# Supplies02.net
KiCad netlist of a schematic drawn in Altium Designer
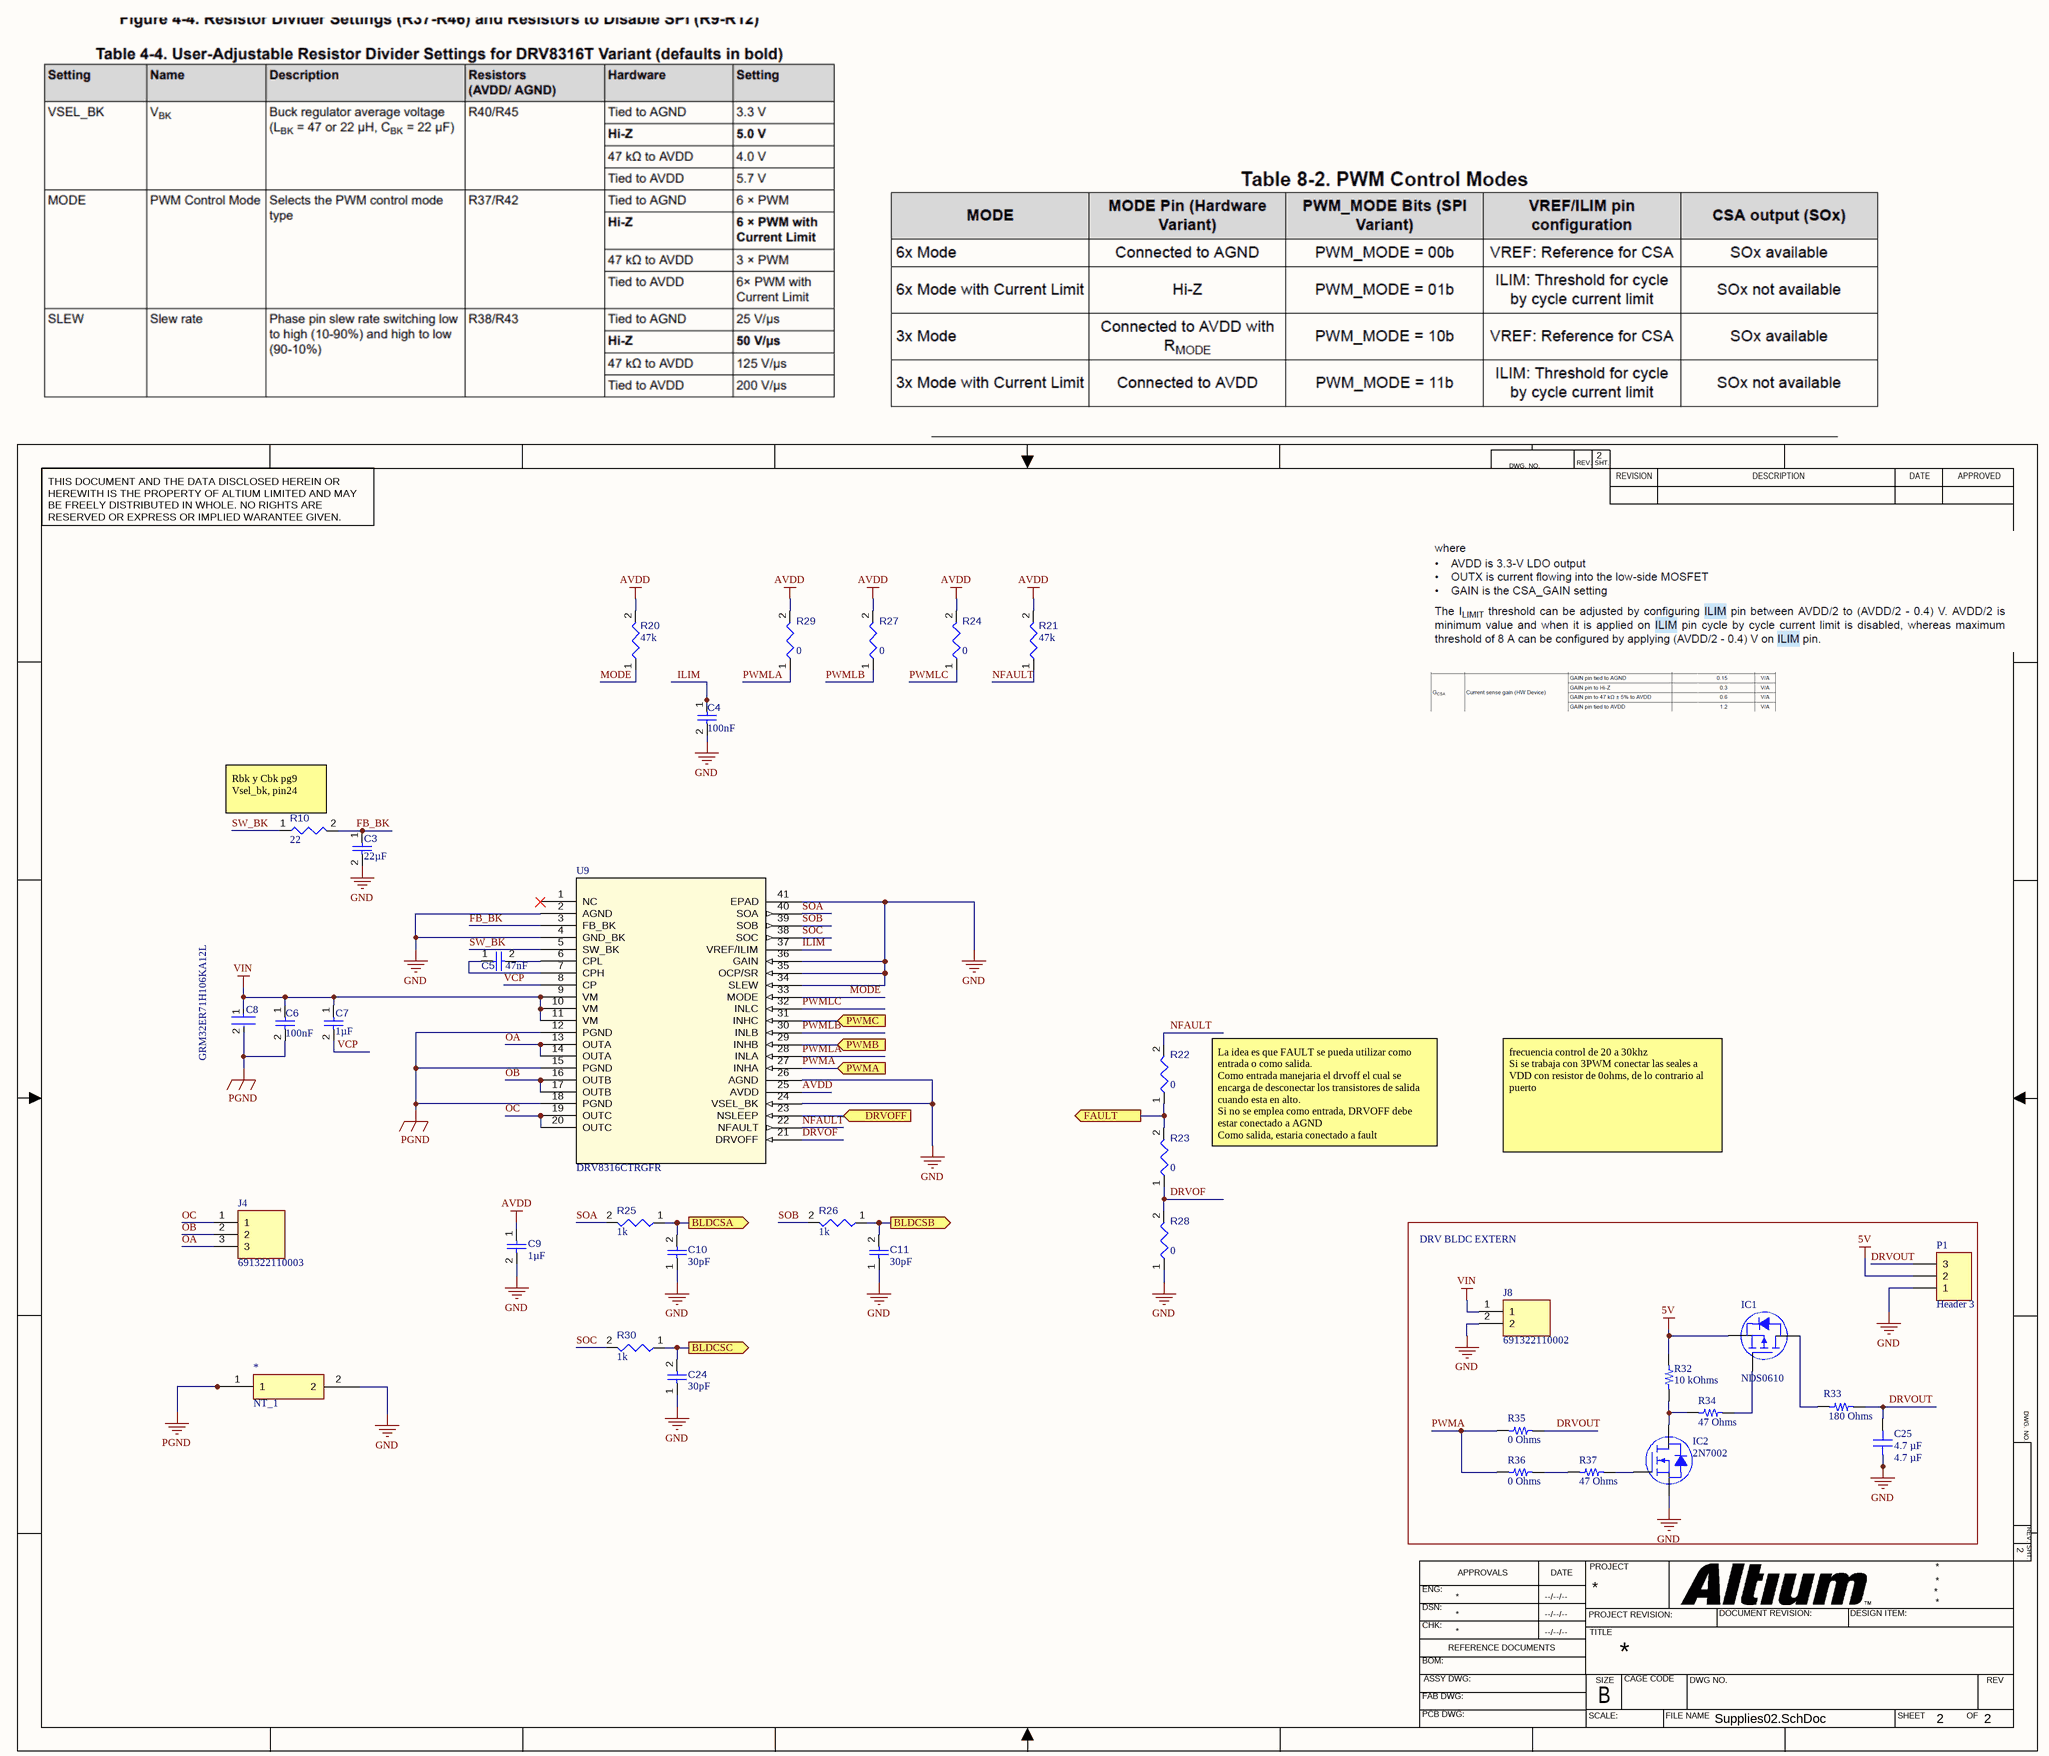
[diagram p0: Supplies02.SchDoc]

(export (version "E")
  (design (tool "Eeschema 10.0.6"))
  (components
    (comp (ref "*") (value "NT_1") (footprint "Net_Tie") (libsource (lib "net_tie") (part "NT_1")))
    (comp (ref "C3")
      (value "22µF")
      (footprint "CAPC0805(2012)145_L")
      (description "Chip Capacitor, 22µF +/-40%, 16V, 0805, Thickness 1.45 mm")
      (fields (field (name "TOLERANCE") "5%") (field (name "Comment") "Capacitor 22µF +/-40% 16V 0805"))
      (libsource (lib "UdeA") (part "CAP-NP-2"))
    )
    (comp (ref "C4")
      (value "100nF")
      (footprint "CAPC1608X90X40NL10T20")
      (description "Chip Capacitor, 100 nF, +/- 10%, 50 V, 0603 (1608 Metric)")
      (fields (field (name "TOLERANCE") "10%") (field (name "Comment") "Capacitor 100 nF +/-10% 50 V 0603"))
      (libsource (lib "UdeA") (part "CAP-NP-2"))
    )
    (comp (ref "C5")
      (value "47nF")
      (footprint "CAPC1608X90X40NL10T20")
      (description "Chip Capacitor, 100 nF, +/- 10%, 50 V, 0603 (1608 Metric)")
      (fields (field (name "TOLERANCE") "10%") (field (name "Comment") "Capacitor 100 nF +/-10% 50 V 0603"))
      (libsource (lib "UdeA") (part "CAP-NP-2"))
    )
    (comp (ref "C6")
      (value "100nF")
      (footprint "CAPC1608X90X40NL10T20")
      (description "Chip Capacitor, 100 nF, +/- 10%, 50 V, 0603 (1608 Metric)")
      (fields (field (name "TOLERANCE") "10%") (field (name "Comment") "Capacitor 100 nF +/-10% 50 V 0603"))
      (libsource (lib "UdeA") (part "CAP-NP-2"))
    )
    (comp (ref "C7")
      (value "1µF")
      (footprint "CAPC0805(2012)145_L")
      (description "Chip Capacitor, 22µF +/-40%, 16V, 0805, Thickness 1.45 mm")
      (fields (field (name "TOLERANCE") "5%") (field (name "Comment") "Capacitor 22µF +/-40% 16V 0805"))
      (libsource (lib "UdeA") (part "CAP-NP-2"))
    )
    (comp (ref "C8")
      (value "GRM32ER71H106KA12L")
      (footprint "FP-GRM32-MFG")
      (description "CAP CER 10UF 50V X7R 1210")
      (fields (field (name "TOLERANCE") "10%") (field (name "MANUFACTURER") "Murata"))
      (libsource (lib "Altium Content Vault") (part "11868f565c42a9108669ba33697ecf6"))
    )
    (comp (ref "C9")
      (value "1µF")
      (footprint "CAPC0805(2012)145_L")
      (description "Chip Capacitor, 22µF +/-40%, 16V, 0805, Thickness 1.45 mm")
      (fields (field (name "TOLERANCE") "5%") (field (name "Comment") "Capacitor 22µF +/-40% 16V 0805"))
      (libsource (lib "UdeA") (part "CAP-NP-2"))
    )
    (comp (ref "C10")
      (value "30pF")
      (footprint "CAPC1608X90X40NL10T20")
      (description "Chip Capacitor, 100 nF, +/- 10%, 50 V, 0603 (1608 Metric)")
      (fields (field (name "TOLERANCE") "10%") (field (name "Comment") "Capacitor 100 nF +/-10% 50 V 0603"))
      (libsource (lib "UdeA") (part "CAP-NP-2"))
    )
    (comp (ref "C11")
      (value "30pF")
      (footprint "CAPC1608X90X40NL10T20")
      (description "Chip Capacitor, 100 nF, +/- 10%, 50 V, 0603 (1608 Metric)")
      (fields (field (name "TOLERANCE") "10%") (field (name "Comment") "Capacitor 100 nF +/-10% 50 V 0603"))
      (libsource (lib "UdeA") (part "CAP-NP-2"))
    )
    (comp (ref "C24")
      (value "30pF")
      (footprint "CAPC1608X90X40NL10T20")
      (description "Chip Capacitor, 100 nF, +/- 10%, 50 V, 0603 (1608 Metric)")
      (fields (field (name "TOLERANCE") "10%") (field (name "Comment") "Capacitor 100 nF +/-10% 50 V 0603"))
      (libsource (lib "UdeA") (part "CAP-NP-2"))
    )
    (comp (ref "C25")
      (value "4.7 µF")
      (footprint "CAP 0805_2012")
      (description "CAP CER 4.7UF 6.3V X7R 0805")
      (fields
        (field (name "PART NUMBER") "C0805X475J9RACAUTO")
        (field (name "CAPACITANCE") "4.7 µF")
        (field (name "MANUFACTURER") "KEMET")
      )
      (libsource (lib "Celestial Altium Library - altium_library") (part "Capacitor"))
    )
    (comp (ref "IC1")
      (value "NDS0610")
      (footprint "ON SEMI SOT-23-3")
      (description "MOSFET P-CH 60V 120MA SOT-23")
      (fields (field (name "MANUFACTURER") "ON Semiconductor"))
      (libsource (lib "Celestial Altium Library - altium_library") (part "ON SEMI MOSFET P-CH SOT-23-3"))
    )
    (comp (ref "IC2")
      (value "2N7002")
      (footprint "ON SEMI SOT-23-3")
      (description "MOSFET N-CH 60V 115MA SOT-23")
      (fields (field (name "MANUFACTURER") "ON Semiconductor"))
      (libsource (lib "Celestial Altium Library - altium_library") (part "ON SEMI MOSFET N-CH SOT-23-3"))
    )
    (comp (ref "J4")
      (value "691322110003")
      (footprint "SHDRRA3W80P0X350_1X3_1190X920X700P")
      (fields (field (name "MOUSER PART NUMBER") "710-691322110003"))
      (libsource (lib "691322110003") (part "691322110003"))
    )
    (comp (ref "J8")
      (value "691322110002")
      (footprint "SHDRRA2W80P0X350_1X2_840X920X720P")
      (description "WR-TBL Terminal block - serie 3221")
      (fields (field (name "MOUSER PART NUMBER") "710-691322110002"))
      (libsource (lib "691322110002") (part "691322110002"))
    )
    (comp (ref "P1")
      (value "Header 3")
      (footprint "HDR1X3")
      (description "Header, 3-Pin")
      (fields (field (name "PUBLISHER") "Altium Limited"))
      (libsource (lib "Miscellaneous Connectors") (part "Header 3"))
    )
    (comp (ref "R10")
      (value "22")
      (footprint "RESC1608X55X25ML10T15")
      (description "Chip Resistor, 10 KOhm, +/- 1%, 01 W, -55 to 155 degC, 0603 (1608 Metric)")
      (fields (field (name "POWER") "100mW") (field (name "TOLERANCE") "1%"))
      (libsource (lib "UdeA") (part "RES-2"))
    )
    (comp (ref "R20")
      (value "47k")
      (footprint "RESC1608X55X25ML10T15")
      (description "Chip Resistor, 10 KOhm, +/- 1%, 01 W, -55 to 155 degC, 0603 (1608 Metric)")
      (fields (field (name "POWER") "100mW") (field (name "TOLERANCE") "1%"))
      (libsource (lib "UdeA") (part "RES-2"))
    )
    (comp (ref "R21")
      (value "47k")
      (footprint "RESC1608X55X25ML10T15")
      (description "Chip Resistor, 10 KOhm, +/- 1%, 01 W, -55 to 155 degC, 0603 (1608 Metric)")
      (fields (field (name "POWER") "100mW") (field (name "TOLERANCE") "1%"))
      (libsource (lib "UdeA") (part "RES-2"))
    )
    (comp (ref "R22")
      (value "0")
      (footprint "RESC1608X55X25ML10T15")
      (description "Chip Resistor, 10 KOhm, +/- 1%, 01 W, -55 to 155 degC, 0603 (1608 Metric)")
      (fields (field (name "POWER") "100mW") (field (name "TOLERANCE") "1%"))
      (libsource (lib "UdeA") (part "RES-2"))
    )
    (comp (ref "R23")
      (value "0")
      (footprint "RESC1608X55X25ML10T15")
      (description "Chip Resistor, 10 KOhm, +/- 1%, 01 W, -55 to 155 degC, 0603 (1608 Metric)")
      (fields (field (name "POWER") "100mW") (field (name "TOLERANCE") "1%"))
      (libsource (lib "UdeA") (part "RES-2"))
    )
    (comp (ref "R24")
      (value "0")
      (footprint "RESC1608X55X25ML10T15")
      (description "Chip Resistor, 10 KOhm, +/- 1%, 01 W, -55 to 155 degC, 0603 (1608 Metric)")
      (fields (field (name "POWER") "100mW") (field (name "TOLERANCE") "1%"))
      (libsource (lib "UdeA") (part "RES-2"))
    )
    (comp (ref "R25")
      (value "1k")
      (footprint "RESC1608X55X25ML10T15")
      (description "Chip Resistor, 10 KOhm, +/- 1%, 01 W, -55 to 155 degC, 0603 (1608 Metric)")
      (fields (field (name "POWER") "100mW") (field (name "TOLERANCE") "1%"))
      (libsource (lib "UdeA") (part "RES-2"))
    )
    (comp (ref "R26")
      (value "1k")
      (footprint "RESC1608X55X25ML10T15")
      (description "Chip Resistor, 10 KOhm, +/- 1%, 01 W, -55 to 155 degC, 0603 (1608 Metric)")
      (fields (field (name "POWER") "100mW") (field (name "TOLERANCE") "1%"))
      (libsource (lib "UdeA") (part "RES-2"))
    )
    (comp (ref "R27")
      (value "0")
      (footprint "RESC1608X55X25ML10T15")
      (description "Chip Resistor, 10 KOhm, +/- 1%, 01 W, -55 to 155 degC, 0603 (1608 Metric)")
      (fields (field (name "POWER") "100mW") (field (name "TOLERANCE") "1%"))
      (libsource (lib "UdeA") (part "RES-2"))
    )
    (comp (ref "R28")
      (value "0")
      (footprint "RESC1608X55X25ML10T15")
      (description "Chip Resistor, 10 KOhm, +/- 1%, 01 W, -55 to 155 degC, 0603 (1608 Metric)")
      (fields (field (name "POWER") "100mW") (field (name "TOLERANCE") "1%"))
      (libsource (lib "UdeA") (part "RES-2"))
    )
    (comp (ref "R29")
      (value "0")
      (footprint "RESC1608X55X25ML10T15")
      (description "Chip Resistor, 10 KOhm, +/- 1%, 01 W, -55 to 155 degC, 0603 (1608 Metric)")
      (fields (field (name "POWER") "100mW") (field (name "TOLERANCE") "1%"))
      (libsource (lib "altium-import") (part "root_1_RES-2_"))
    )
    (comp (ref "R30")
      (value "1k")
      (footprint "RESC1608X55X25ML10T15")
      (description "Chip Resistor, 10 KOhm, +/- 1%, 01 W, -55 to 155 degC, 0603 (1608 Metric)")
      (fields (field (name "POWER") "100mW") (field (name "TOLERANCE") "1%"))
      (libsource (lib "UdeA") (part "RES-2"))
    )
    (comp (ref "R32")
      (value "10 kOhms")
      (footprint "YAGEO RES 0603_1608")
      (description "RES SMD 10K OHM 0.5% 1/10W 0603")
      (fields (field (name "PART NUMBER") "RT0603DRD0710KL") (field (name "MANUFACTURER") "Yageo"))
      (libsource (lib "Celestial Altium Library - altium_library") (part "Resistor"))
    )
    (comp (ref "R33")
      (value "180 Ohms")
      (footprint "YAGEO RES 0603_1608")
      (description "RES SMD 180 OHM 0.1% 1/10W 0603")
      (fields (field (name "PART NUMBER") "RT0603BRD07180RL") (field (name "MANUFACTURER") "Yageo"))
      (libsource (lib "Celestial Altium Library - altium_library") (part "Resistor"))
    )
    (comp (ref "R34")
      (value "47 Ohms")
      (footprint "YAGEO RES 0603_1608")
      (description "RES 47 OHM 5% 1/4W 0603")
      (fields (field (name "PART NUMBER") "SR0603JR-7T47RL") (field (name "MANUFACTURER") "Yageo"))
      (libsource (lib "Celestial Altium Library - altium_library") (part "Resistor"))
    )
    (comp (ref "R35")
      (value "0 Ohms")
      (footprint "YAGEO RES 0603_1608")
      (description "RES 0 OHM JUMPER 1/2W 0603")
      (fields (field (name "PART NUMBER") "PA0603-R-070RL") (field (name "MANUFACTURER") "Yageo"))
      (libsource (lib "Celestial Altium Library - altium_library") (part "Resistor"))
    )
    (comp (ref "R36")
      (value "0 Ohms")
      (footprint "YAGEO RES 0603_1608")
      (description "RES 0 OHM JUMPER 1/2W 0603")
      (fields (field (name "PART NUMBER") "PA0603-R-070RL") (field (name "MANUFACTURER") "Yageo"))
      (libsource (lib "Celestial Altium Library - altium_library") (part "Resistor"))
    )
    (comp (ref "R37")
      (value "47 Ohms")
      (footprint "YAGEO RES 0603_1608")
      (description "RES 47 OHM 5% 1/4W 0603")
      (fields (field (name "PART NUMBER") "SR0603JR-7T47RL") (field (name "MANUFACTURER") "Yageo"))
      (libsource (lib "Celestial Altium Library - altium_library") (part "Resistor"))
    )
    (comp (ref "U9")
      (value "DRV8316CTRGFR")
      (footprint "VQFN40_RGF_TEX")
      (description "No Description Available")
      (fields (field (name "COPYRIGHT") "Copyright (C) 2024 Ultra Librarian. All rights reserved."))
      (libsource (lib "DRV8316CTRGFR") (part "DRV8316CTRGFR"))
    )
  )
  (nets
    (net (code "1") (name "/BLDCSA") (class "Default")
      (node (ref "C10") (pin "2") (pinfunction "2_2") (pintype "passive"))
      (node (ref "R25") (pin "1") (pinfunction "1_1") (pintype "passive"))
    )
    (net (code "2") (name "/BLDCSB") (class "Default")
      (node (ref "C11") (pin "2") (pinfunction "2_2") (pintype "passive"))
      (node (ref "R26") (pin "1") (pinfunction "1_1") (pintype "passive"))
    )
    (net (code "3") (name "/BLDCSC") (class "Default")
      (node (ref "C24") (pin "2") (pinfunction "2_2") (pintype "passive"))
      (node (ref "R30") (pin "1") (pinfunction "1_1") (pintype "passive"))
    )
    (net (code "4") (name "/DRVOF") (class "Default")
      (node (ref "R23") (pin "1") (pinfunction "1_1") (pintype "passive"))
      (node (ref "R28") (pin "2") (pinfunction "2_2") (pintype "passive"))
      (node (ref "U9") (pin "21") (pinfunction "DRVOFF_21") (pintype "input"))
    )
    (net (code "5") (name "/DRVOFF") (class "Default")
      (node (ref "U9") (pin "23") (pinfunction "NSLEEP_23") (pintype "input"))
    )
    (net (code "6") (name "/DRVOUT") (class "Default")
      (node (ref "C25") (pin "2") (pinfunction "2_2") (pintype "passive"))
      (node (ref "P1") (pin "3") (pinfunction "3_3") (pintype "passive"))
      (node (ref "R33") (pin "2") (pinfunction "2_2") (pintype "passive"))
      (node (ref "R35") (pin "2") (pinfunction "2_2") (pintype "passive"))
    )
    (net (code "7") (name "/FAULT") (class "Default")
      (node (ref "R22") (pin "1") (pinfunction "1_1") (pintype "passive"))
      (node (ref "R23") (pin "2") (pinfunction "2_2") (pintype "passive"))
    )
    (net (code "8") (name "/FB_BK") (class "Default")
      (node (ref "C3") (pin "1") (pinfunction "1_1") (pintype "passive"))
      (node (ref "R10") (pin "2") (pinfunction "2_2") (pintype "passive"))
      (node (ref "U9") (pin "3") (pinfunction "FB_BK_3") (pintype "power_in"))
    )
    (net (code "9") (name "/ILIM") (class "Default")
      (node (ref "C4") (pin "1") (pinfunction "1_1") (pintype "passive"))
      (node (ref "U9") (pin "37") (pinfunction "VREF/ILIM_37") (pintype "power_in"))
    )
    (net (code "10") (name "/MODE") (class "Default")
      (node (ref "R20") (pin "1") (pinfunction "1_1") (pintype "passive"))
      (node (ref "U9") (pin "33") (pinfunction "MODE_33") (pintype "input"))
    )
    (net (code "11") (name "/NFAULT") (class "Default")
      (node (ref "R21") (pin "1") (pinfunction "1_1") (pintype "passive"))
      (node (ref "R22") (pin "2") (pinfunction "2_2") (pintype "passive"))
      (node (ref "U9") (pin "22") (pinfunction "NFAULT_22") (pintype "output"))
    )
    (net (code "12") (name "/OA") (class "Default")
      (node (ref "J4") (pin "3") (pinfunction "3_3") (pintype "passive"))
      (node (ref "U9") (pin "13") (pinfunction "OUTA_13") (pintype "power_in"))
      (node (ref "U9") (pin "14") (pinfunction "OUTA_14") (pintype "power_in"))
    )
    (net (code "13") (name "/OB") (class "Default")
      (node (ref "J4") (pin "2") (pinfunction "2_2") (pintype "passive"))
      (node (ref "U9") (pin "16") (pinfunction "OUTB_16") (pintype "power_in"))
      (node (ref "U9") (pin "17") (pinfunction "OUTB_17") (pintype "power_in"))
    )
    (net (code "14") (name "/OC") (class "Default")
      (node (ref "J4") (pin "1") (pinfunction "1_1") (pintype "passive"))
      (node (ref "U9") (pin "19") (pinfunction "OUTC_19") (pintype "power_in"))
      (node (ref "U9") (pin "20") (pinfunction "OUTC_20") (pintype "power_in"))
    )
    (net (code "15") (name "/PWMA") (class "Default")
      (node (ref "R35") (pin "1") (pinfunction "1_1") (pintype "passive"))
      (node (ref "R36") (pin "1") (pinfunction "1_1") (pintype "passive"))
      (node (ref "U9") (pin "27") (pinfunction "INHA_27") (pintype "input"))
    )
    (net (code "16") (name "/PWMB") (class "Default")
      (node (ref "U9") (pin "29") (pinfunction "INHB_29") (pintype "input"))
    )
    (net (code "17") (name "/PWMC") (class "Default")
      (node (ref "U9") (pin "31") (pinfunction "INHC_31") (pintype "input"))
    )
    (net (code "18") (name "/PWMLA") (class "Default")
      (node (ref "R29") (pin "1") (pinfunction "1_1") (pintype "passive"))
      (node (ref "U9") (pin "28") (pinfunction "INLA_28") (pintype "input"))
    )
    (net (code "19") (name "/PWMLB") (class "Default")
      (node (ref "R27") (pin "1") (pinfunction "1_1") (pintype "passive"))
      (node (ref "U9") (pin "30") (pinfunction "INLB_30") (pintype "input"))
    )
    (net (code "20") (name "/PWMLC") (class "Default")
      (node (ref "R24") (pin "1") (pinfunction "1_1") (pintype "passive"))
      (node (ref "U9") (pin "32") (pinfunction "INLC_32") (pintype "input"))
    )
    (net (code "21") (name "/SOA") (class "Default")
      (node (ref "R25") (pin "2") (pinfunction "2_2") (pintype "passive"))
      (node (ref "U9") (pin "40") (pinfunction "SOA_40") (pintype "output"))
    )
    (net (code "22") (name "/SOB") (class "Default")
      (node (ref "R26") (pin "2") (pinfunction "2_2") (pintype "passive"))
      (node (ref "U9") (pin "39") (pinfunction "SOB_39") (pintype "output"))
    )
    (net (code "23") (name "/SOC") (class "Default")
      (node (ref "R30") (pin "2") (pinfunction "2_2") (pintype "passive"))
      (node (ref "U9") (pin "38") (pinfunction "SOC_38") (pintype "output"))
    )
    (net (code "24") (name "/SW_BK") (class "Default")
      (node (ref "R10") (pin "1") (pinfunction "1_1") (pintype "passive"))
      (node (ref "U9") (pin "5") (pinfunction "SW_BK_5") (pintype "power_in"))
    )
    (net (code "25") (name "/VCP") (class "Default")
      (node (ref "C7") (pin "2") (pinfunction "2_2") (pintype "passive"))
      (node (ref "U9") (pin "8") (pinfunction "CP_8") (pintype "power_in"))
    )
    (net (code "26") (name "5V") (class "Default")
      (node (ref "IC1") (pin "2") (pinfunction "S_2") (pintype "passive"))
      (node (ref "P1") (pin "2") (pinfunction "2_2") (pintype "passive"))
      (node (ref "R32") (pin "2") (pinfunction "2_2") (pintype "passive"))
    )
    (net (code "27") (name "AVDD") (class "Default")
      (node (ref "C9") (pin "1") (pinfunction "1_1") (pintype "passive"))
      (node (ref "R20") (pin "2") (pinfunction "2_2") (pintype "passive"))
      (node (ref "R21") (pin "2") (pinfunction "2_2") (pintype "passive"))
      (node (ref "R24") (pin "2") (pinfunction "2_2") (pintype "passive"))
      (node (ref "R27") (pin "2") (pinfunction "2_2") (pintype "passive"))
      (node (ref "R29") (pin "2") (pinfunction "2_2") (pintype "passive"))
      (node (ref "U9") (pin "25") (pinfunction "AVDD_25") (pintype "power_in"))
    )
    (net (code "28") (name "GND") (class "Default")
      (node (ref "*") (pin "2") (pinfunction "2_2") (pintype "passive"))
      (node (ref "C10") (pin "1") (pinfunction "1_1") (pintype "passive"))
      (node (ref "C11") (pin "1") (pinfunction "1_1") (pintype "passive"))
      (node (ref "C24") (pin "1") (pinfunction "1_1") (pintype "passive"))
      (node (ref "C25") (pin "1") (pinfunction "1_1") (pintype "passive"))
      (node (ref "C3") (pin "2") (pinfunction "2_2") (pintype "passive"))
      (node (ref "C4") (pin "2") (pinfunction "2_2") (pintype "passive"))
      (node (ref "C9") (pin "2") (pinfunction "2_2") (pintype "passive"))
      (node (ref "IC2") (pin "2") (pinfunction "S_2") (pintype "passive"))
      (node (ref "J8") (pin "2") (pinfunction "2_2") (pintype "passive"))
      (node (ref "P1") (pin "1") (pinfunction "1_1") (pintype "passive"))
      (node (ref "R28") (pin "1") (pinfunction "1_1") (pintype "passive"))
      (node (ref "U9") (pin "2") (pinfunction "AGND_2") (pintype "power_in"))
      (node (ref "U9") (pin "24") (pinfunction "VSEL_BK_24") (pintype "input"))
      (node (ref "U9") (pin "26") (pinfunction "AGND_26") (pintype "power_in"))
      (node (ref "U9") (pin "34") (pinfunction "SLEW_34") (pintype "input"))
      (node (ref "U9") (pin "35") (pinfunction "OCP/SR_35") (pintype "input"))
      (node (ref "U9") (pin "36") (pinfunction "GAIN_36") (pintype "input"))
      (node (ref "U9") (pin "4") (pinfunction "GND_BK_4") (pintype "power_in"))
      (node (ref "U9") (pin "41") (pinfunction "EPAD_41") (pintype "power_in"))
    )
    (net (code "29") (name "Net-(IC1-D)") (class "Default")
      (node (ref "IC1") (pin "3") (pinfunction "D_3") (pintype "passive"))
      (node (ref "R33") (pin "1") (pinfunction "1_1") (pintype "passive"))
    )
    (net (code "30") (name "Net-(IC1-G)") (class "Default")
      (node (ref "IC1") (pin "1") (pinfunction "G_1") (pintype "passive"))
      (node (ref "R34") (pin "2") (pinfunction "2_2") (pintype "passive"))
    )
    (net (code "31") (name "Net-(IC2-D)") (class "Default")
      (node (ref "IC2") (pin "3") (pinfunction "D_3") (pintype "passive"))
      (node (ref "R32") (pin "1") (pinfunction "1_1") (pintype "passive"))
      (node (ref "R34") (pin "1") (pinfunction "1_1") (pintype "passive"))
    )
    (net (code "32") (name "Net-(IC2-G)") (class "Default")
      (node (ref "IC2") (pin "1") (pinfunction "G_1") (pintype "passive"))
      (node (ref "R37") (pin "2") (pinfunction "2_2") (pintype "passive"))
    )
    (net (code "33") (name "Net-(R36-Pad2)") (class "Default")
      (node (ref "R36") (pin "2") (pinfunction "2_2") (pintype "passive"))
      (node (ref "R37") (pin "1") (pinfunction "1_1") (pintype "passive"))
    )
    (net (code "34") (name "Net-(U9-CPH)") (class "Default")
      (node (ref "C5") (pin "1") (pinfunction "1_1") (pintype "passive"))
      (node (ref "U9") (pin "7") (pinfunction "CPH_7") (pintype "power_in"))
    )
    (net (code "35") (name "Net-(U9-CPL)") (class "Default")
      (node (ref "C5") (pin "2") (pinfunction "2_2") (pintype "passive"))
      (node (ref "U9") (pin "6") (pinfunction "CPL_6") (pintype "power_in"))
    )
    (net (code "36") (name "PGND") (class "Default")
      (node (ref "*") (pin "1") (pinfunction "1_1") (pintype "passive"))
      (node (ref "C6") (pin "2") (pinfunction "2_2") (pintype "passive"))
      (node (ref "C8") (pin "2") (pinfunction "2_2") (pintype "passive"))
      (node (ref "U9") (pin "12") (pinfunction "PGND_12") (pintype "power_in"))
      (node (ref "U9") (pin "15") (pinfunction "PGND_15") (pintype "power_in"))
      (node (ref "U9") (pin "18") (pinfunction "PGND_18") (pintype "power_in"))
    )
    (net (code "37") (name "VIN") (class "Default")
      (node (ref "C6") (pin "1") (pinfunction "1_1") (pintype "passive"))
      (node (ref "C7") (pin "1") (pinfunction "1_1") (pintype "passive"))
      (node (ref "C8") (pin "1") (pinfunction "1_1") (pintype "passive"))
      (node (ref "J8") (pin "1") (pinfunction "1_1") (pintype "passive"))
      (node (ref "U9") (pin "10") (pinfunction "VM_10") (pintype "power_in"))
      (node (ref "U9") (pin "11") (pinfunction "VM_11") (pintype "power_in"))
      (node (ref "U9") (pin "9") (pinfunction "VM_9") (pintype "power_in"))
    )
    (net (code "38") (name "unconnected-(U9-NC-Pad1)") (class "Default")
      (node (ref "U9") (pin "1") (pinfunction "NC_1") (pintype "passive+no_connect"))
    )
  )
)
